# I2C_Multiplexers.net
KiCad netlist of a schematic drawn in Altium Designer
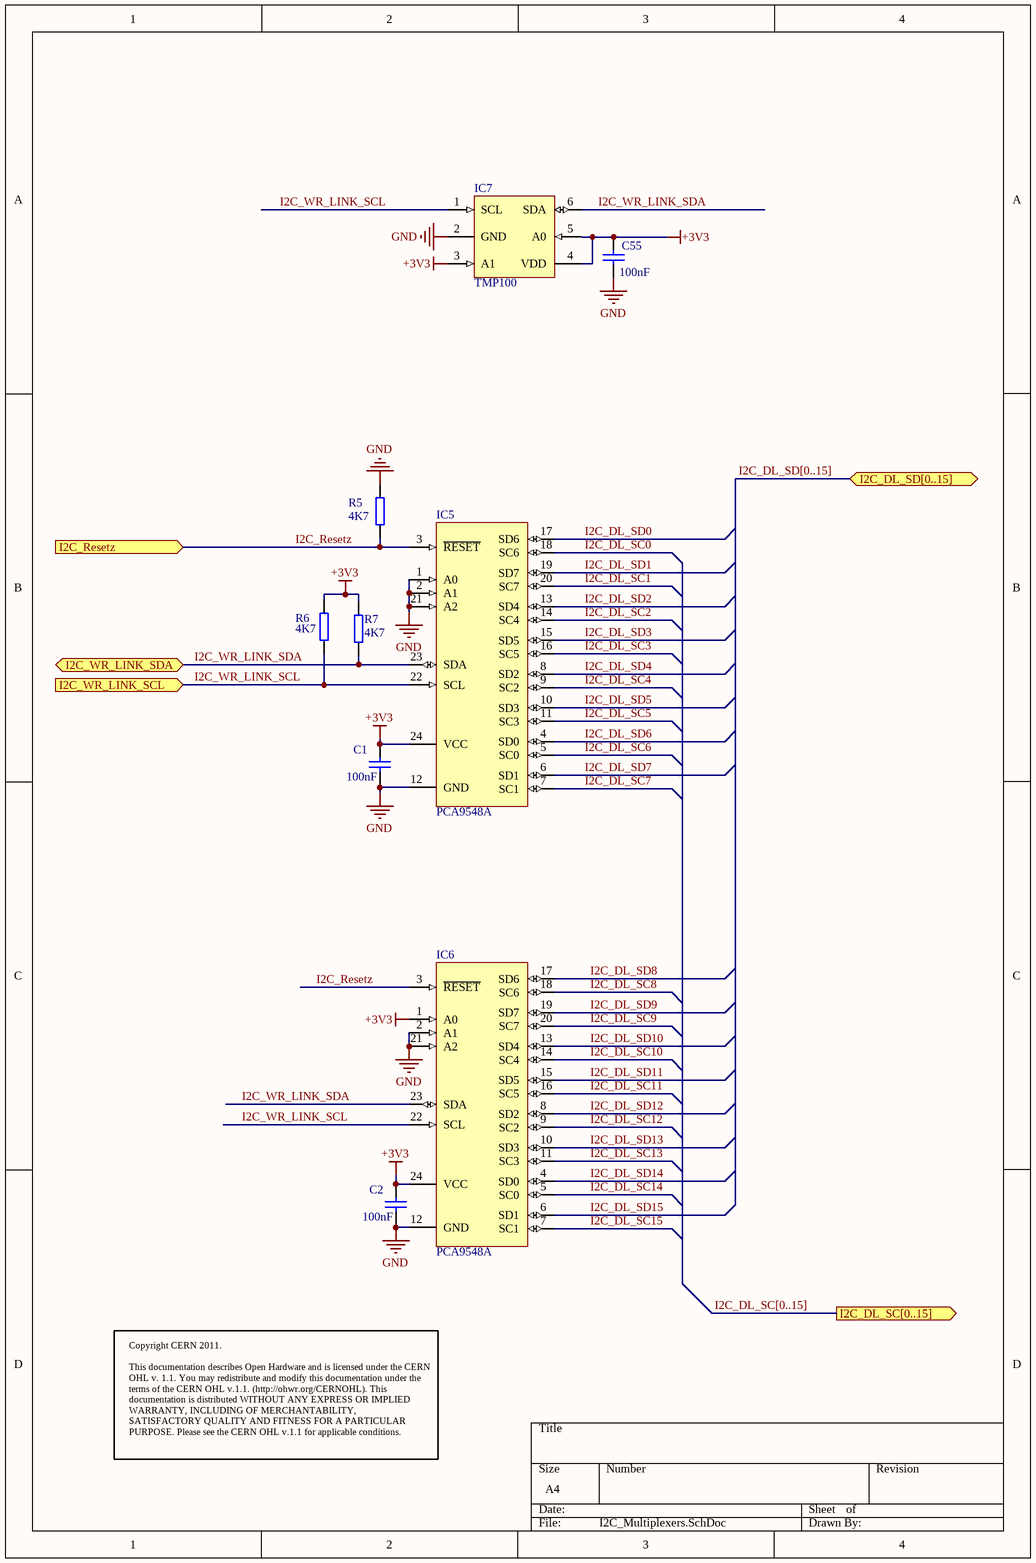
[diagram p0: I2C_Multiplexers.SchDoc]

(export (version "E")
  (design (tool "Eeschema 10.0.6"))
  (components
    (comp (ref "C1")
      (value "100nF")
      (footprint "CC1608-0603")
      (description "Capacitor")
      (fields
        (field (name "TOLERANCE") "±10%")
        (field (name "VOLTAGE") "16V")
        (field (name "PUBLISHER") "Altium Limited")
      )
      (libsource (lib "wr_switch") (part "Cap"))
    )
    (comp (ref "C2")
      (value "100nF")
      (footprint "CC1608-0603")
      (description "Capacitor")
      (fields
        (field (name "TOLERANCE") "±10%")
        (field (name "VOLTAGE") "16V")
        (field (name "PUBLISHER") "Altium Limited")
      )
      (libsource (lib "wr_switch") (part "Cap"))
    )
    (comp (ref "C55")
      (value "100nF")
      (footprint "CC1608-0603")
      (description "Capacitor")
      (fields
        (field (name "TOLERANCE") "±10%")
        (field (name "VOLTAGE") "16V")
        (field (name "PUBLISHER") "Altium Limited")
      )
      (libsource (lib "wr_switch") (part "Cap"))
    )
    (comp (ref "IC5")
      (value "PCA9548A")
      (footprint "SOP65P640X120-24N")
      (description "8-channel 2C-bus switch with reset")
      (libsource (lib "wr_switch") (part "PCA9548A"))
    )
    (comp (ref "IC6")
      (value "PCA9548A")
      (footprint "SOP65P640X120-24N")
      (description "8-channel 2C-bus switch with reset")
      (libsource (lib "wr_switch") (part "PCA9548A"))
    )
    (comp (ref "IC7")
      (value "TMP100")
      (footprint "SOT23A-6L")
      (description "I2C temp. sensor")
      (libsource (lib "wr_switch") (part "TMP100"))
    )
    (comp (ref "R5")
      (value "4K7")
      (footprint "0603")
      (description "SMD Resistor")
      (fields (field (name "TOLERANCE") "±1%"))
      (libsource (lib "wr_switch") (part "RES_SMD"))
    )
    (comp (ref "R6")
      (value "4K7")
      (footprint "0603")
      (description "SMD Resistor")
      (fields (field (name "TOLERANCE") "±1%"))
      (libsource (lib "wr_switch") (part "RES_SMD"))
    )
    (comp (ref "R7")
      (value "4K7")
      (footprint "0603")
      (description "SMD Resistor")
      (fields (field (name "TOLERANCE") "±1%"))
      (libsource (lib "wr_switch") (part "RES_SMD"))
    )
  )
  (nets
    (net (code "1") (name "+3V3") (class "Default")
      (node (ref "C1") (pin "2") (pinfunction "2_2") (pintype "passive"))
      (node (ref "C2") (pin "2") (pinfunction "2_2") (pintype "passive"))
      (node (ref "C55") (pin "2") (pinfunction "2_2") (pintype "passive"))
      (node (ref "IC5") (pin "24") (pinfunction "VCC_24") (pintype "power_in"))
      (node (ref "IC6") (pin "1") (pinfunction "A0_1") (pintype "input"))
      (node (ref "IC6") (pin "24") (pinfunction "VCC_24") (pintype "power_in"))
      (node (ref "IC7") (pin "3") (pinfunction "A1_3") (pintype "input"))
      (node (ref "IC7") (pin "4") (pinfunction "VDD_4") (pintype "power_in"))
      (node (ref "IC7") (pin "5") (pinfunction "A0_5") (pintype "input"))
      (node (ref "R6") (pin "1") (pinfunction "1_1") (pintype "passive"))
      (node (ref "R7") (pin "1") (pinfunction "1_1") (pintype "passive"))
    )
    (net (code "2") (name "/I2C_DL_SC0") (class "Default")
      (node (ref "IC5") (pin "18") (pinfunction "SC6_18") (pintype "bidirectional"))
    )
    (net (code "3") (name "/I2C_DL_SC1") (class "Default")
      (node (ref "IC5") (pin "20") (pinfunction "SC7_20") (pintype "bidirectional"))
    )
    (net (code "4") (name "/I2C_DL_SC2") (class "Default")
      (node (ref "IC5") (pin "14") (pinfunction "SC4_14") (pintype "bidirectional"))
    )
    (net (code "5") (name "/I2C_DL_SC3") (class "Default")
      (node (ref "IC5") (pin "16") (pinfunction "SC5_16") (pintype "bidirectional"))
    )
    (net (code "6") (name "/I2C_DL_SC4") (class "Default")
      (node (ref "IC5") (pin "9") (pinfunction "SC2_9") (pintype "bidirectional"))
    )
    (net (code "7") (name "/I2C_DL_SC5") (class "Default")
      (node (ref "IC5") (pin "11") (pinfunction "SC3_11") (pintype "bidirectional"))
    )
    (net (code "8") (name "/I2C_DL_SC6") (class "Default")
      (node (ref "IC5") (pin "5") (pinfunction "SC0_5") (pintype "bidirectional"))
    )
    (net (code "9") (name "/I2C_DL_SC7") (class "Default")
      (node (ref "IC5") (pin "7") (pinfunction "SC1_7") (pintype "bidirectional"))
    )
    (net (code "10") (name "/I2C_DL_SC8") (class "Default")
      (node (ref "IC6") (pin "18") (pinfunction "SC6_18") (pintype "bidirectional"))
    )
    (net (code "11") (name "/I2C_DL_SC9") (class "Default")
      (node (ref "IC6") (pin "20") (pinfunction "SC7_20") (pintype "bidirectional"))
    )
    (net (code "12") (name "/I2C_DL_SC10") (class "Default")
      (node (ref "IC6") (pin "14") (pinfunction "SC4_14") (pintype "bidirectional"))
    )
    (net (code "13") (name "/I2C_DL_SC11") (class "Default")
      (node (ref "IC6") (pin "16") (pinfunction "SC5_16") (pintype "bidirectional"))
    )
    (net (code "14") (name "/I2C_DL_SC12") (class "Default")
      (node (ref "IC6") (pin "9") (pinfunction "SC2_9") (pintype "bidirectional"))
    )
    (net (code "15") (name "/I2C_DL_SC13") (class "Default")
      (node (ref "IC6") (pin "11") (pinfunction "SC3_11") (pintype "bidirectional"))
    )
    (net (code "16") (name "/I2C_DL_SC14") (class "Default")
      (node (ref "IC6") (pin "5") (pinfunction "SC0_5") (pintype "bidirectional"))
    )
    (net (code "17") (name "/I2C_DL_SC15") (class "Default")
      (node (ref "IC6") (pin "7") (pinfunction "SC1_7") (pintype "bidirectional"))
    )
    (net (code "19") (name "/I2C_DL_SD0") (class "Default")
      (node (ref "IC5") (pin "17") (pinfunction "SD6_17") (pintype "bidirectional"))
    )
    (net (code "20") (name "/I2C_DL_SD1") (class "Default")
      (node (ref "IC5") (pin "19") (pinfunction "SD7_19") (pintype "bidirectional"))
    )
    (net (code "21") (name "/I2C_DL_SD2") (class "Default")
      (node (ref "IC5") (pin "13") (pinfunction "SD4_13") (pintype "bidirectional"))
    )
    (net (code "22") (name "/I2C_DL_SD3") (class "Default")
      (node (ref "IC5") (pin "15") (pinfunction "SD5_15") (pintype "bidirectional"))
    )
    (net (code "23") (name "/I2C_DL_SD4") (class "Default")
      (node (ref "IC5") (pin "8") (pinfunction "SD2_8") (pintype "bidirectional"))
    )
    (net (code "24") (name "/I2C_DL_SD5") (class "Default")
      (node (ref "IC5") (pin "10") (pinfunction "SD3_10") (pintype "bidirectional"))
    )
    (net (code "25") (name "/I2C_DL_SD6") (class "Default")
      (node (ref "IC5") (pin "4") (pinfunction "SD0_4") (pintype "bidirectional"))
    )
    (net (code "26") (name "/I2C_DL_SD7") (class "Default")
      (node (ref "IC5") (pin "6") (pinfunction "SD1_6") (pintype "bidirectional"))
    )
    (net (code "27") (name "/I2C_DL_SD8") (class "Default")
      (node (ref "IC6") (pin "17") (pinfunction "SD6_17") (pintype "bidirectional"))
    )
    (net (code "28") (name "/I2C_DL_SD9") (class "Default")
      (node (ref "IC6") (pin "19") (pinfunction "SD7_19") (pintype "bidirectional"))
    )
    (net (code "29") (name "/I2C_DL_SD10") (class "Default")
      (node (ref "IC6") (pin "13") (pinfunction "SD4_13") (pintype "bidirectional"))
    )
    (net (code "30") (name "/I2C_DL_SD11") (class "Default")
      (node (ref "IC6") (pin "15") (pinfunction "SD5_15") (pintype "bidirectional"))
    )
    (net (code "31") (name "/I2C_DL_SD12") (class "Default")
      (node (ref "IC6") (pin "8") (pinfunction "SD2_8") (pintype "bidirectional"))
    )
    (net (code "32") (name "/I2C_DL_SD13") (class "Default")
      (node (ref "IC6") (pin "10") (pinfunction "SD3_10") (pintype "bidirectional"))
    )
    (net (code "33") (name "/I2C_DL_SD14") (class "Default")
      (node (ref "IC6") (pin "4") (pinfunction "SD0_4") (pintype "bidirectional"))
    )
    (net (code "34") (name "/I2C_DL_SD15") (class "Default")
      (node (ref "IC6") (pin "6") (pinfunction "SD1_6") (pintype "bidirectional"))
    )
    (net (code "36") (name "/I2C_Resetz") (class "Default")
      (node (ref "IC5") (pin "3") (pinfunction "~{RESET}_3") (pintype "input"))
      (node (ref "IC6") (pin "3") (pinfunction "~{RESET}_3") (pintype "input"))
      (node (ref "R5") (pin "1") (pinfunction "1_1") (pintype "passive"))
    )
    (net (code "37") (name "/I2C_WR_LINK_SCL") (class "Default")
      (node (ref "IC5") (pin "22") (pinfunction "SCL_22") (pintype "input"))
      (node (ref "IC6") (pin "22") (pinfunction "SCL_22") (pintype "input"))
      (node (ref "IC7") (pin "1") (pinfunction "SCL_1") (pintype "input"))
      (node (ref "R6") (pin "2") (pinfunction "2_2") (pintype "passive"))
    )
    (net (code "38") (name "/I2C_WR_LINK_SDA") (class "Default")
      (node (ref "IC5") (pin "23") (pinfunction "SDA_23") (pintype "bidirectional"))
      (node (ref "IC6") (pin "23") (pinfunction "SDA_23") (pintype "bidirectional"))
      (node (ref "IC7") (pin "6") (pinfunction "SDA_6") (pintype "bidirectional"))
      (node (ref "R7") (pin "2") (pinfunction "2_2") (pintype "passive"))
    )
    (net (code "39") (name "GND") (class "Default")
      (node (ref "C1") (pin "1") (pinfunction "1_1") (pintype "passive"))
      (node (ref "C2") (pin "1") (pinfunction "1_1") (pintype "passive"))
      (node (ref "C55") (pin "1") (pinfunction "1_1") (pintype "passive"))
      (node (ref "IC5") (pin "1") (pinfunction "A0_1") (pintype "input"))
      (node (ref "IC5") (pin "12") (pinfunction "GND_12") (pintype "power_in"))
      (node (ref "IC5") (pin "2") (pinfunction "A1_2") (pintype "input"))
      (node (ref "IC5") (pin "21") (pinfunction "A2_21") (pintype "input"))
      (node (ref "IC6") (pin "12") (pinfunction "GND_12") (pintype "power_in"))
      (node (ref "IC6") (pin "2") (pinfunction "A1_2") (pintype "input"))
      (node (ref "IC6") (pin "21") (pinfunction "A2_21") (pintype "input"))
      (node (ref "IC7") (pin "2") (pinfunction "GND_2") (pintype "power_in"))
      (node (ref "R5") (pin "2") (pinfunction "2_2") (pintype "passive"))
    )
  )
)
